# gps_tracker_org1411.net
KiCad netlist of a schematic drawn in EAGLE
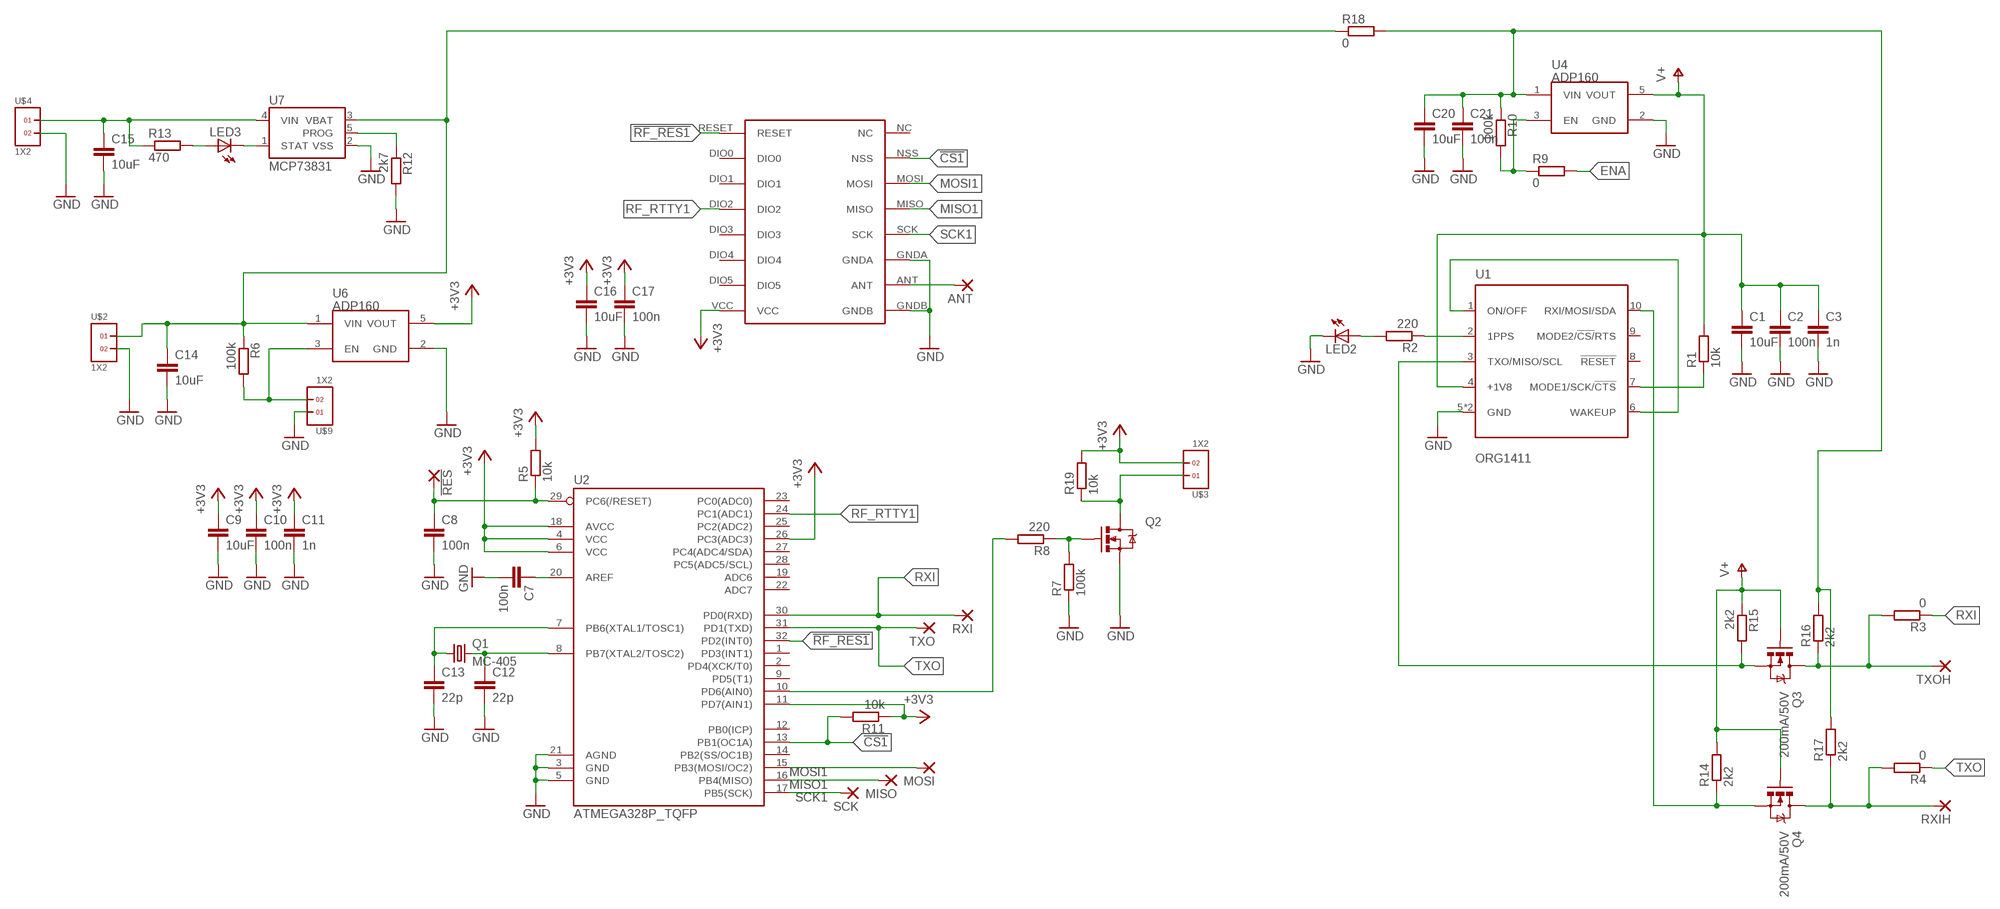
[diagram p0: schematic, sheet 1]

(export (version "E")
  (design (tool "Eeschema 10.0.6"))
  (components
    (comp (ref "!RES")
      (value "SMD2")
      (footprint "eagle-import:SMD1,27-2,54")
      (libsource (lib "eagle-import") (part "SMD2"))
    )
    (comp (ref "ANT")
      (value "SMD2")
      (footprint "eagle-import:SMD1,27-2,54")
      (libsource (lib "eagle-import") (part "SMD2"))
    )
    (comp (ref "C1")
      (value "10uF")
      (footprint "eagle-import:C0603")
      (libsource (lib "eagle-import") (part "C-EUC0603"))
    )
    (comp (ref "C2")
      (value "100n")
      (footprint "eagle-import:C0603")
      (libsource (lib "eagle-import") (part "C-EUC0603"))
    )
    (comp (ref "C3")
      (value "1n")
      (footprint "eagle-import:C0603")
      (libsource (lib "eagle-import") (part "C-EUC0603"))
    )
    (comp (ref "C7")
      (value "100n")
      (footprint "eagle-import:C0603")
      (libsource (lib "eagle-import") (part "C-EUC0603"))
    )
    (comp (ref "C8")
      (value "100n")
      (footprint "eagle-import:C0603")
      (libsource (lib "eagle-import") (part "C-EUC0603"))
    )
    (comp (ref "C9")
      (value "10uF")
      (footprint "eagle-import:C0603")
      (libsource (lib "eagle-import") (part "C-EUC0603"))
    )
    (comp (ref "C10")
      (value "100n")
      (footprint "eagle-import:C0603")
      (libsource (lib "eagle-import") (part "C-EUC0603"))
    )
    (comp (ref "C11")
      (value "1n")
      (footprint "eagle-import:C0603")
      (libsource (lib "eagle-import") (part "C-EUC0603"))
    )
    (comp (ref "C12")
      (value "22p")
      (footprint "eagle-import:C0603")
      (libsource (lib "eagle-import") (part "C-EUC0603"))
    )
    (comp (ref "C13")
      (value "22p")
      (footprint "eagle-import:C0603")
      (libsource (lib "eagle-import") (part "C-EUC0603"))
    )
    (comp (ref "C14")
      (value "10uF")
      (footprint "eagle-import:C0603")
      (libsource (lib "eagle-import") (part "C-EUC0603"))
    )
    (comp (ref "C15")
      (value "10uF")
      (footprint "eagle-import:C0603")
      (libsource (lib "eagle-import") (part "C-EUC0603"))
    )
    (comp (ref "C16")
      (value "10uF")
      (footprint "eagle-import:C0603")
      (libsource (lib "eagle-import") (part "C-EUC0603"))
    )
    (comp (ref "C17")
      (value "100n")
      (footprint "eagle-import:C0603")
      (libsource (lib "eagle-import") (part "C-EUC0603"))
    )
    (comp (ref "C20")
      (value "10uF")
      (footprint "eagle-import:C0603")
      (libsource (lib "eagle-import") (part "C-EUC0603"))
    )
    (comp (ref "C21")
      (value "100n")
      (footprint "eagle-import:C0603")
      (libsource (lib "eagle-import") (part "C-EUC0603"))
    )
    (comp (ref "LED2")
      (value "LEDCHIPLED_0603")
      (footprint "eagle-import:CHIPLED_0603")
      (libsource (lib "eagle-import") (part "LEDCHIPLED_0603"))
    )
    (comp (ref "LED3")
      (value "LEDCHIPLED_0603")
      (footprint "eagle-import:CHIPLED_0603")
      (libsource (lib "eagle-import") (part "LEDCHIPLED_0603"))
    )
    (comp (ref "MISO")
      (value "SMD2")
      (footprint "eagle-import:SMD1,27-2,54")
      (libsource (lib "eagle-import") (part "SMD2"))
    )
    (comp (ref "MOSI")
      (value "SMD2")
      (footprint "eagle-import:SMD1,27-2,54")
      (libsource (lib "eagle-import") (part "SMD2"))
    )
    (comp (ref "Q1")
      (value "MC-405")
      (footprint "eagle-import:MC-405")
      (libsource (lib "eagle-import") (part "MC-405"))
    )
    (comp (ref "Q2")
      (value "MOSFET-NCHANNELAO3404A")
      (footprint "eagle-import:SOT23-3")
      (libsource (lib "eagle-import") (part "MOSFET-NCHANNELAO3404A"))
    )
    (comp (ref "Q3")
      (value "200mA/50V")
      (footprint "eagle-import:SOT23-3")
      (libsource (lib "eagle-import") (part "MOSFET-NCHANNELBSS138"))
    )
    (comp (ref "Q4")
      (value "200mA/50V")
      (footprint "eagle-import:SOT23-3")
      (libsource (lib "eagle-import") (part "MOSFET-NCHANNELBSS138"))
    )
    (comp (ref "R1")
      (value "10k")
      (footprint "eagle-import:R0603")
      (libsource (lib "eagle-import") (part "R-EU_R0603"))
    )
    (comp (ref "R2")
      (value "220")
      (footprint "eagle-import:R0603")
      (libsource (lib "eagle-import") (part "R-EU_R0603"))
    )
    (comp (ref "R3")
      (value "0")
      (footprint "eagle-import:R0603")
      (libsource (lib "eagle-import") (part "R-EU_R0603"))
    )
    (comp (ref "R4")
      (value "0")
      (footprint "eagle-import:R0603")
      (libsource (lib "eagle-import") (part "R-EU_R0603"))
    )
    (comp (ref "R5")
      (value "10k")
      (footprint "eagle-import:R0603")
      (libsource (lib "eagle-import") (part "R-EU_R0603"))
    )
    (comp (ref "R6")
      (value "100k")
      (footprint "eagle-import:R0603")
      (libsource (lib "eagle-import") (part "R-EU_R0603"))
    )
    (comp (ref "R7")
      (value "100k")
      (footprint "eagle-import:R0603")
      (libsource (lib "eagle-import") (part "R-EU_R0603"))
    )
    (comp (ref "R8")
      (value "220")
      (footprint "eagle-import:R0603")
      (libsource (lib "eagle-import") (part "R-EU_R0603"))
    )
    (comp (ref "R9")
      (value "0")
      (footprint "eagle-import:R0603")
      (libsource (lib "eagle-import") (part "R-EU_R0603"))
    )
    (comp (ref "R10")
      (value "100k")
      (footprint "eagle-import:R0603")
      (libsource (lib "eagle-import") (part "R-EU_R0603"))
    )
    (comp (ref "R11")
      (value "10k")
      (footprint "eagle-import:R0603")
      (libsource (lib "eagle-import") (part "R-EU_R0603"))
    )
    (comp (ref "R12")
      (value "2k7")
      (footprint "eagle-import:R0603")
      (libsource (lib "eagle-import") (part "R-EU_R0603"))
    )
    (comp (ref "R13")
      (value "470")
      (footprint "eagle-import:R0603")
      (libsource (lib "eagle-import") (part "R-EU_R0603"))
    )
    (comp (ref "R14")
      (value "2k2")
      (footprint "eagle-import:R0603")
      (libsource (lib "eagle-import") (part "R-EU_R0603"))
    )
    (comp (ref "R15")
      (value "2k2")
      (footprint "eagle-import:R0603")
      (libsource (lib "eagle-import") (part "R-EU_R0603"))
    )
    (comp (ref "R16")
      (value "2k2")
      (footprint "eagle-import:R1206")
      (libsource (lib "eagle-import") (part "R-EU_R1206"))
    )
    (comp (ref "R17")
      (value "2k2")
      (footprint "eagle-import:R1206")
      (libsource (lib "eagle-import") (part "R-EU_R1206"))
    )
    (comp (ref "R18")
      (value "0")
      (footprint "eagle-import:R0603")
      (libsource (lib "eagle-import") (part "R-EU_R0603"))
    )
    (comp (ref "R19")
      (value "10k")
      (footprint "eagle-import:R0603")
      (libsource (lib "eagle-import") (part "R-EU_R0603"))
    )
    (comp (ref "RXI")
      (value "SMD2")
      (footprint "eagle-import:SMD1,27-2,54")
      (libsource (lib "eagle-import") (part "SMD2"))
    )
    (comp (ref "RXIH")
      (value "SMD2")
      (footprint "eagle-import:SMD1,27-2,54")
      (libsource (lib "eagle-import") (part "SMD2"))
    )
    (comp (ref "SCK")
      (value "SMD2")
      (footprint "eagle-import:SMD1,27-2,54")
      (libsource (lib "eagle-import") (part "SMD2"))
    )
    (comp (ref "TXO")
      (value "SMD2")
      (footprint "eagle-import:SMD1,27-2,54")
      (libsource (lib "eagle-import") (part "SMD2"))
    )
    (comp (ref "TXOH")
      (value "SMD2")
      (footprint "eagle-import:SMD1,27-2,54")
      (libsource (lib "eagle-import") (part "SMD2"))
    )
    (comp (ref "U$2")
      (value "1X2")
      (footprint "eagle-import:1X2")
      (libsource (lib "eagle-import") (part "1X2"))
    )
    (comp (ref "U$3")
      (value "1X2")
      (footprint "eagle-import:1X2")
      (libsource (lib "eagle-import") (part "1X2"))
    )
    (comp (ref "U$4")
      (value "1X2")
      (footprint "eagle-import:1X2")
      (libsource (lib "eagle-import") (part "1X2"))
    )
    (comp (ref "U$5")
      (value "RFM69HW")
      (footprint "eagle-import:RFM")
      (libsource (lib "eagle-import") (part "RFM69HW"))
    )
    (comp (ref "U$9")
      (value "1X2")
      (footprint "eagle-import:1X2")
      (libsource (lib "eagle-import") (part "1X2"))
    )
    (comp (ref "U1")
      (value "ORG1411")
      (footprint "eagle-import:ORG1411")
      (libsource (lib "eagle-import") (part "ORG1411"))
    )
    (comp (ref "U2")
      (value "ATMEGA328P_TQFP")
      (footprint "eagle-import:TQFP32-08")
      (libsource (lib "eagle-import") (part "ATMEGA328P_TQFP"))
    )
    (comp (ref "U4")
      (value "ADP160")
      (footprint "eagle-import:SOT23-5")
      (libsource (lib "eagle-import") (part "ADP160"))
    )
    (comp (ref "U6")
      (value "ADP160")
      (footprint "eagle-import:SOT23-5")
      (libsource (lib "eagle-import") (part "ADP160"))
    )
    (comp (ref "U7")
      (value "MCP73831")
      (footprint "eagle-import:SOT23-5")
      (libsource (lib "eagle-import") (part "MCP73831"))
    )
  )
  (nets
    (net (code "1") (name "+3V3") (class "Default")
      (node (ref "C10") (pin "1") (pinfunction "1_1") (pintype "passive"))
      (node (ref "C11") (pin "1") (pinfunction "1_1") (pintype "passive"))
      (node (ref "C16") (pin "1") (pinfunction "1_1") (pintype "passive"))
      (node (ref "C17") (pin "1") (pinfunction "1_1") (pintype "passive"))
      (node (ref "C9") (pin "1") (pinfunction "1_1") (pintype "passive"))
      (node (ref "R11") (pin "1") (pinfunction "1_1") (pintype "passive"))
      (node (ref "R19") (pin "2") (pinfunction "2_2") (pintype "passive"))
      (node (ref "R5") (pin "2") (pinfunction "2_2") (pintype "passive"))
      (node (ref "U$3") (pin "2") (pinfunction "2_2") (pintype "bidirectional"))
      (node (ref "U$5") (pin "VCC") (pinfunction "VCC_VCC") (pintype "bidirectional"))
      (node (ref "U2") (pin "11") (pinfunction "PD7(AIN1)_11") (pintype "bidirectional"))
      (node (ref "U2") (pin "18") (pinfunction "AVCC_18") (pintype "bidirectional"))
      (node (ref "U2") (pin "26") (pinfunction "PC3(ADC3)_26") (pintype "bidirectional"))
      (node (ref "U2") (pin "4") (pinfunction "VCC_4") (pintype "bidirectional"))
      (node (ref "U2") (pin "6") (pinfunction "VCC_6") (pintype "bidirectional"))
      (node (ref "U6") (pin "5") (pinfunction "VOUT_5") (pintype "bidirectional"))
    )
    (net (code "2") (name "ENA") (class "Default")
      (node (ref "R6") (pin "2") (pinfunction "2_2") (pintype "passive"))
      (node (ref "R9") (pin "2") (pinfunction "2_2") (pintype "passive"))
      (node (ref "U$9") (pin "2") (pinfunction "2_2") (pintype "bidirectional"))
      (node (ref "U6") (pin "3") (pinfunction "EN_3") (pintype "bidirectional"))
    )
    (net (code "3") (name "GND") (class "Default")
      (node (ref "C1") (pin "2") (pinfunction "2_2") (pintype "passive"))
      (node (ref "C10") (pin "2") (pinfunction "2_2") (pintype "passive"))
      (node (ref "C11") (pin "2") (pinfunction "2_2") (pintype "passive"))
      (node (ref "C12") (pin "2") (pinfunction "2_2") (pintype "passive"))
      (node (ref "C13") (pin "2") (pinfunction "2_2") (pintype "passive"))
      (node (ref "C14") (pin "2") (pinfunction "2_2") (pintype "passive"))
      (node (ref "C15") (pin "2") (pinfunction "2_2") (pintype "passive"))
      (node (ref "C16") (pin "2") (pinfunction "2_2") (pintype "passive"))
      (node (ref "C17") (pin "2") (pinfunction "2_2") (pintype "passive"))
      (node (ref "C2") (pin "2") (pinfunction "2_2") (pintype "passive"))
      (node (ref "C20") (pin "2") (pinfunction "2_2") (pintype "passive"))
      (node (ref "C21") (pin "2") (pinfunction "2_2") (pintype "passive"))
      (node (ref "C3") (pin "2") (pinfunction "2_2") (pintype "passive"))
      (node (ref "C7") (pin "2") (pinfunction "2_2") (pintype "passive"))
      (node (ref "C8") (pin "2") (pinfunction "2_2") (pintype "passive"))
      (node (ref "C9") (pin "2") (pinfunction "2_2") (pintype "passive"))
      (node (ref "LED2") (pin "C") (pinfunction "C_C") (pintype "passive"))
      (node (ref "Q2") (pin "2") (pinfunction "S_2") (pintype "passive"))
      (node (ref "R12") (pin "2") (pinfunction "2_2") (pintype "passive"))
      (node (ref "R7") (pin "1") (pinfunction "1_1") (pintype "passive"))
      (node (ref "U$2") (pin "2") (pinfunction "2_2") (pintype "bidirectional"))
      (node (ref "U$4") (pin "2") (pinfunction "2_2") (pintype "bidirectional"))
      (node (ref "U$5") (pin "GNDA") (pinfunction "GNDA_GNDA") (pintype "bidirectional"))
      (node (ref "U$5") (pin "GNDB") (pinfunction "GNDB_GNDB") (pintype "bidirectional"))
      (node (ref "U$9") (pin "1") (pinfunction "1_1") (pintype "bidirectional"))
      (node (ref "U1") (pin "11") (pinfunction "GND_11") (pintype "power_in"))
      (node (ref "U1") (pin "5") (pinfunction "GND_5") (pintype "power_in"))
      (node (ref "U2") (pin "21") (pinfunction "AGND_21") (pintype "bidirectional"))
      (node (ref "U2") (pin "3") (pinfunction "GND_3") (pintype "bidirectional"))
      (node (ref "U2") (pin "5") (pinfunction "GND_5") (pintype "bidirectional"))
      (node (ref "U4") (pin "2") (pinfunction "GND_2") (pintype "bidirectional"))
      (node (ref "U6") (pin "2") (pinfunction "GND_2") (pintype "bidirectional"))
      (node (ref "U7") (pin "2") (pinfunction "VSS_2") (pintype "power_in"))
    )
    (net (code "4") (name "MISO1") (class "Default")
      (node (ref "MISO") (pin "1") (pinfunction "P_1") (pintype "passive"))
      (node (ref "U$5") (pin "MISO") (pinfunction "MISO_MISO") (pintype "bidirectional"))
      (node (ref "U2") (pin "16") (pinfunction "PB4(MISO)_16") (pintype "bidirectional"))
    )
    (net (code "5") (name "MOSI1") (class "Default")
      (node (ref "MOSI") (pin "1") (pinfunction "P_1") (pintype "passive"))
      (node (ref "U$5") (pin "MOSI") (pinfunction "MOSI_MOSI") (pintype "bidirectional"))
      (node (ref "U2") (pin "15") (pinfunction "PB3(MOSI/OC2)_15") (pintype "bidirectional"))
    )
    (net (code "6") (name "Net-(!RES-P)") (class "Default")
      (node (ref "!RES") (pin "1") (pinfunction "P_1") (pintype "passive"))
      (node (ref "C8") (pin "1") (pinfunction "1_1") (pintype "passive"))
      (node (ref "R5") (pin "1") (pinfunction "1_1") (pintype "passive"))
      (node (ref "U2") (pin "29") (pinfunction "PC6(/RESET)_29") (pintype "bidirectional"))
    )
    (net (code "7") (name "Net-(ANT-P)") (class "Default")
      (node (ref "ANT") (pin "1") (pinfunction "P_1") (pintype "passive"))
      (node (ref "U$5") (pin "ANT") (pinfunction "ANT_ANT") (pintype "bidirectional"))
    )
    (net (code "8") (name "Net-(LED2-PadA)") (class "Default")
      (node (ref "LED2") (pin "A") (pinfunction "A_A") (pintype "passive"))
      (node (ref "R2") (pin "2") (pinfunction "2_2") (pintype "passive"))
    )
    (net (code "9") (name "Net-(LED3-PadA)") (class "Default")
      (node (ref "LED3") (pin "A") (pinfunction "A_A") (pintype "passive"))
      (node (ref "R13") (pin "2") (pinfunction "2_2") (pintype "passive"))
    )
    (net (code "10") (name "Net-(Q2-D)") (class "Default")
      (node (ref "Q2") (pin "3") (pinfunction "D_3") (pintype "passive"))
      (node (ref "R19") (pin "1") (pinfunction "1_1") (pintype "passive"))
      (node (ref "U$3") (pin "1") (pinfunction "1_1") (pintype "bidirectional"))
    )
    (net (code "11") (name "Net-(Q2-G)") (class "Default")
      (node (ref "Q2") (pin "1") (pinfunction "G_1") (pintype "passive"))
      (node (ref "R7") (pin "2") (pinfunction "2_2") (pintype "passive"))
      (node (ref "R8") (pin "1") (pinfunction "1_1") (pintype "passive"))
    )
    (net (code "12") (name "Net-(Q3-D)") (class "Default")
      (node (ref "Q3") (pin "3") (pinfunction "D_3") (pintype "passive"))
      (node (ref "R16") (pin "1") (pinfunction "1_1") (pintype "passive"))
      (node (ref "R3") (pin "2") (pinfunction "2_2") (pintype "passive"))
      (node (ref "TXOH") (pin "1") (pinfunction "P_1") (pintype "passive"))
    )
    (net (code "13") (name "Net-(Q3-S)") (class "Default")
      (node (ref "Q3") (pin "2") (pinfunction "S_2") (pintype "passive"))
      (node (ref "R15") (pin "2") (pinfunction "2_2") (pintype "passive"))
      (node (ref "U1") (pin "3") (pinfunction "TXO/MISO/SCL_3") (pintype "bidirectional"))
    )
    (net (code "14") (name "Net-(Q4-D)") (class "Default")
      (node (ref "Q4") (pin "3") (pinfunction "D_3") (pintype "passive"))
      (node (ref "R17") (pin "1") (pinfunction "1_1") (pintype "passive"))
      (node (ref "R4") (pin "2") (pinfunction "2_2") (pintype "passive"))
      (node (ref "RXIH") (pin "1") (pinfunction "P_1") (pintype "passive"))
    )
    (net (code "15") (name "Net-(Q4-S)") (class "Default")
      (node (ref "Q4") (pin "2") (pinfunction "S_2") (pintype "passive"))
      (node (ref "R14") (pin "1") (pinfunction "1_1") (pintype "passive"))
      (node (ref "U1") (pin "10") (pinfunction "RXI/MOSI/SDA_10") (pintype "bidirectional"))
    )
    (net (code "16") (name "Net-(U1-1PPS)") (class "Default")
      (node (ref "R2") (pin "1") (pinfunction "1_1") (pintype "passive"))
      (node (ref "U1") (pin "2") (pinfunction "1PPS_2") (pintype "output"))
    )
    (net (code "17") (name "Net-(U1-MODE1{slash}SCK{slash}~{CTS})") (class "Default")
      (node (ref "R1") (pin "1") (pinfunction "1_1") (pintype "passive"))
      (node (ref "U1") (pin "7") (pinfunction "MODE1/SCK/~{CTS}_7") (pintype "bidirectional"))
    )
    (net (code "18") (name "Net-(U1-ON{slash}OFF)") (class "Default")
      (node (ref "U1") (pin "1") (pinfunction "ON/OFF_1") (pintype "input"))
      (node (ref "U1") (pin "6") (pinfunction "WAKEUP_6") (pintype "output"))
    )
    (net (code "19") (name "Net-(U2-AREF)") (class "Default")
      (node (ref "C7") (pin "1") (pinfunction "1_1") (pintype "passive"))
      (node (ref "U2") (pin "20") (pinfunction "AREF_20") (pintype "bidirectional"))
    )
    (net (code "20") (name "Net-(U2-PB6(XTAL1{slash}TOSC1))") (class "Default")
      (node (ref "C13") (pin "1") (pinfunction "1_1") (pintype "passive"))
      (node (ref "Q1") (pin "1") (pinfunction "1_1") (pintype "passive"))
      (node (ref "U2") (pin "7") (pinfunction "PB6(XTAL1/TOSC1)_7") (pintype "bidirectional"))
    )
    (net (code "21") (name "Net-(U2-PB7(XTAL2{slash}TOSC2))") (class "Default")
      (node (ref "C12") (pin "1") (pinfunction "1_1") (pintype "passive"))
      (node (ref "Q1") (pin "2") (pinfunction "2_2") (pintype "passive"))
      (node (ref "U2") (pin "8") (pinfunction "PB7(XTAL2/TOSC2)_8") (pintype "bidirectional"))
    )
    (net (code "22") (name "Net-(U2-PD6(AIN0))") (class "Default")
      (node (ref "R8") (pin "2") (pinfunction "2_2") (pintype "passive"))
      (node (ref "U2") (pin "10") (pinfunction "PD6(AIN0)_10") (pintype "bidirectional"))
    )
    (net (code "23") (name "Net-(U4-EN)") (class "Default")
      (node (ref "R10") (pin "2") (pinfunction "2_2") (pintype "passive"))
      (node (ref "R9") (pin "1") (pinfunction "1_1") (pintype "passive"))
      (node (ref "U4") (pin "3") (pinfunction "EN_3") (pintype "bidirectional"))
    )
    (net (code "24") (name "Net-(U4-VIN)") (class "Default")
      (node (ref "C20") (pin "1") (pinfunction "1_1") (pintype "passive"))
      (node (ref "C21") (pin "1") (pinfunction "1_1") (pintype "passive"))
      (node (ref "R10") (pin "1") (pinfunction "1_1") (pintype "passive"))
      (node (ref "R16") (pin "2") (pinfunction "2_2") (pintype "passive"))
      (node (ref "R17") (pin "2") (pinfunction "2_2") (pintype "passive"))
      (node (ref "R18") (pin "2") (pinfunction "2_2") (pintype "passive"))
      (node (ref "U4") (pin "1") (pinfunction "VIN_1") (pintype "bidirectional"))
    )
    (net (code "25") (name "Net-(U6-VIN)") (class "Default")
      (node (ref "C14") (pin "1") (pinfunction "1_1") (pintype "passive"))
      (node (ref "R18") (pin "1") (pinfunction "1_1") (pintype "passive"))
      (node (ref "R6") (pin "1") (pinfunction "1_1") (pintype "passive"))
      (node (ref "U$2") (pin "1") (pinfunction "1_1") (pintype "bidirectional"))
      (node (ref "U6") (pin "1") (pinfunction "VIN_1") (pintype "bidirectional"))
      (node (ref "U7") (pin "3") (pinfunction "VBAT_3") (pintype "power_in"))
    )
    (net (code "26") (name "Net-(U7-PROG)") (class "Default")
      (node (ref "R12") (pin "1") (pinfunction "1_1") (pintype "passive"))
      (node (ref "U7") (pin "5") (pinfunction "PROG_5") (pintype "input"))
    )
    (net (code "27") (name "Net-(U7-STAT)") (class "Default")
      (node (ref "LED3") (pin "C") (pinfunction "C_C") (pintype "passive"))
      (node (ref "U7") (pin "1") (pinfunction "STAT_1") (pintype "output"))
    )
    (net (code "28") (name "Net-(U7-VIN)") (class "Default")
      (node (ref "C15") (pin "1") (pinfunction "1_1") (pintype "passive"))
      (node (ref "R13") (pin "1") (pinfunction "1_1") (pintype "passive"))
      (node (ref "U$4") (pin "1") (pinfunction "1_1") (pintype "bidirectional"))
      (node (ref "U7") (pin "4") (pinfunction "VIN_4") (pintype "power_in"))
    )
    (net (code "29") (name "RF_RTTY1") (class "Default")
      (node (ref "U$5") (pin "DIO2") (pinfunction "DIO2_DIO2") (pintype "bidirectional"))
      (node (ref "U2") (pin "24") (pinfunction "PC1(ADC1)_24") (pintype "bidirectional"))
    )
    (net (code "30") (name "RXI") (class "Default")
      (node (ref "R3") (pin "1") (pinfunction "1_1") (pintype "passive"))
      (node (ref "RXI") (pin "1") (pinfunction "P_1") (pintype "passive"))
      (node (ref "U2") (pin "30") (pinfunction "PD0(RXD)_30") (pintype "bidirectional"))
    )
    (net (code "31") (name "SCK1") (class "Default")
      (node (ref "SCK") (pin "1") (pinfunction "P_1") (pintype "passive"))
      (node (ref "U$5") (pin "SCK") (pinfunction "SCK_SCK") (pintype "bidirectional"))
      (node (ref "U2") (pin "17") (pinfunction "PB5(SCK)_17") (pintype "bidirectional"))
    )
    (net (code "32") (name "TXO") (class "Default")
      (node (ref "R4") (pin "1") (pinfunction "1_1") (pintype "passive"))
      (node (ref "TXO") (pin "1") (pinfunction "P_1") (pintype "passive"))
      (node (ref "U2") (pin "31") (pinfunction "PD1(TXD)_31") (pintype "bidirectional"))
    )
    (net (code "33") (name "V+") (class "Default")
      (node (ref "C1") (pin "1") (pinfunction "1_1") (pintype "passive"))
      (node (ref "C2") (pin "1") (pinfunction "1_1") (pintype "passive"))
      (node (ref "C3") (pin "1") (pinfunction "1_1") (pintype "passive"))
      (node (ref "Q3") (pin "1") (pinfunction "G_1") (pintype "passive"))
      (node (ref "Q4") (pin "1") (pinfunction "G_1") (pintype "passive"))
      (node (ref "R1") (pin "2") (pinfunction "2_2") (pintype "passive"))
      (node (ref "R14") (pin "2") (pinfunction "2_2") (pintype "passive"))
      (node (ref "R15") (pin "1") (pinfunction "1_1") (pintype "passive"))
      (node (ref "U1") (pin "4") (pinfunction "+1V8_4") (pintype "power_in"))
      (node (ref "U4") (pin "5") (pinfunction "VOUT_5") (pintype "bidirectional"))
    )
    (net (code "34") (name "unconnected-(U$5-PadDIO0)") (class "Default")
      (node (ref "U$5") (pin "DIO0") (pinfunction "DIO0_DIO0") (pintype "bidirectional"))
    )
    (net (code "35") (name "unconnected-(U$5-PadDIO1)") (class "Default")
      (node (ref "U$5") (pin "DIO1") (pinfunction "DIO1_DIO1") (pintype "bidirectional"))
    )
    (net (code "36") (name "unconnected-(U$5-PadDIO3)") (class "Default")
      (node (ref "U$5") (pin "DIO3") (pinfunction "DIO3_DIO3") (pintype "bidirectional"))
    )
    (net (code "37") (name "unconnected-(U$5-PadDIO4)") (class "Default")
      (node (ref "U$5") (pin "DIO4") (pinfunction "DIO4_DIO4") (pintype "bidirectional"))
    )
    (net (code "38") (name "unconnected-(U$5-PadDIO5)") (class "Default")
      (node (ref "U$5") (pin "DIO5") (pinfunction "DIO5_DIO5") (pintype "bidirectional"))
    )
    (net (code "39") (name "unconnected-(U$5-PadNC)") (class "Default")
      (node (ref "U$5") (pin "NC") (pinfunction "NC_NC") (pintype "bidirectional"))
    )
    (net (code "40") (name "unconnected-(U1-MODE2{slash}~{CS{slash}}RTS-Pad9)") (class "Default")
      (node (ref "U1") (pin "9") (pinfunction "MODE2/~{CS/}RTS_9") (pintype "bidirectional"))
    )
    (net (code "41") (name "unconnected-(U1-~{RESET}-Pad8)") (class "Default")
      (node (ref "U1") (pin "8") (pinfunction "~{RESET}_8") (pintype "input"))
    )
    (net (code "42") (name "unconnected-(U2-ADC6-Pad19)") (class "Default")
      (node (ref "U2") (pin "19") (pinfunction "ADC6_19") (pintype "bidirectional"))
    )
    (net (code "43") (name "unconnected-(U2-ADC7-Pad22)") (class "Default")
      (node (ref "U2") (pin "22") (pinfunction "ADC7_22") (pintype "bidirectional"))
    )
    (net (code "44") (name "unconnected-(U2-PB0(ICP)-Pad12)") (class "Default")
      (node (ref "U2") (pin "12") (pinfunction "PB0(ICP)_12") (pintype "bidirectional"))
    )
    (net (code "45") (name "unconnected-(U2-PB2(SS{slash}OC1B)-Pad14)") (class "Default")
      (node (ref "U2") (pin "14") (pinfunction "PB2(SS/OC1B)_14") (pintype "bidirectional"))
    )
    (net (code "46") (name "unconnected-(U2-PC0(ADC0)-Pad23)") (class "Default")
      (node (ref "U2") (pin "23") (pinfunction "PC0(ADC0)_23") (pintype "bidirectional"))
    )
    (net (code "47") (name "unconnected-(U2-PC2(ADC2)-Pad25)") (class "Default")
      (node (ref "U2") (pin "25") (pinfunction "PC2(ADC2)_25") (pintype "bidirectional"))
    )
    (net (code "48") (name "unconnected-(U2-PC4(ADC4{slash}SDA)-Pad27)") (class "Default")
      (node (ref "U2") (pin "27") (pinfunction "PC4(ADC4/SDA)_27") (pintype "bidirectional"))
    )
    (net (code "49") (name "unconnected-(U2-PC5(ADC5{slash}SCL)-Pad28)") (class "Default")
      (node (ref "U2") (pin "28") (pinfunction "PC5(ADC5/SCL)_28") (pintype "bidirectional"))
    )
    (net (code "50") (name "unconnected-(U2-PD3(INT1)-Pad1)") (class "Default")
      (node (ref "U2") (pin "1") (pinfunction "PD3(INT1)_1") (pintype "bidirectional"))
    )
    (net (code "51") (name "unconnected-(U2-PD4(XCK{slash}T0)-Pad2)") (class "Default")
      (node (ref "U2") (pin "2") (pinfunction "PD4(XCK/T0)_2") (pintype "bidirectional"))
    )
    (net (code "52") (name "unconnected-(U2-PD5(T1)-Pad9)") (class "Default")
      (node (ref "U2") (pin "9") (pinfunction "PD5(T1)_9") (pintype "bidirectional"))
    )
    (net (code "53") (name "~{CS1}") (class "Default")
      (node (ref "R11") (pin "2") (pinfunction "2_2") (pintype "passive"))
      (node (ref "U$5") (pin "NSS") (pinfunction "NSS_NSS") (pintype "bidirectional"))
      (node (ref "U2") (pin "13") (pinfunction "PB1(OC1A)_13") (pintype "bidirectional"))
    )
    (net (code "54") (name "~{RF_RES1}") (class "Default")
      (node (ref "U$5") (pin "RESET") (pinfunction "RESET_RESET") (pintype "bidirectional"))
      (node (ref "U2") (pin "32") (pinfunction "PD2(INT0)_32") (pintype "bidirectional"))
    )
  )
)
